# 09.net
KiCad netlist of a schematic drawn in Altium Designer
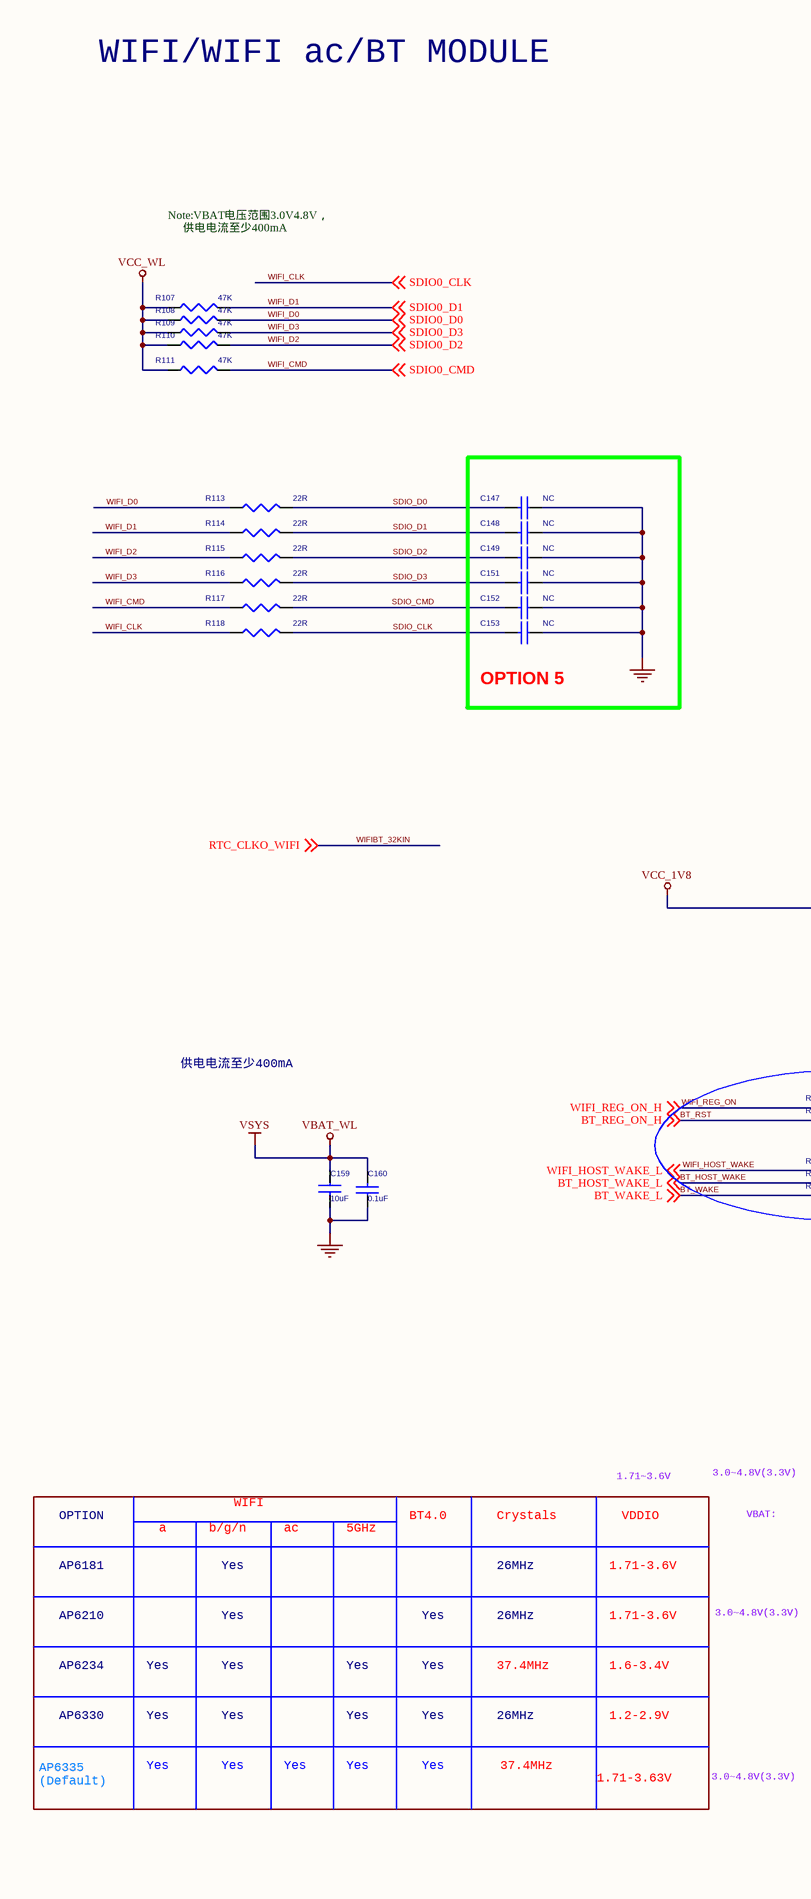
[diagram p0: 09.SchDoc, left]
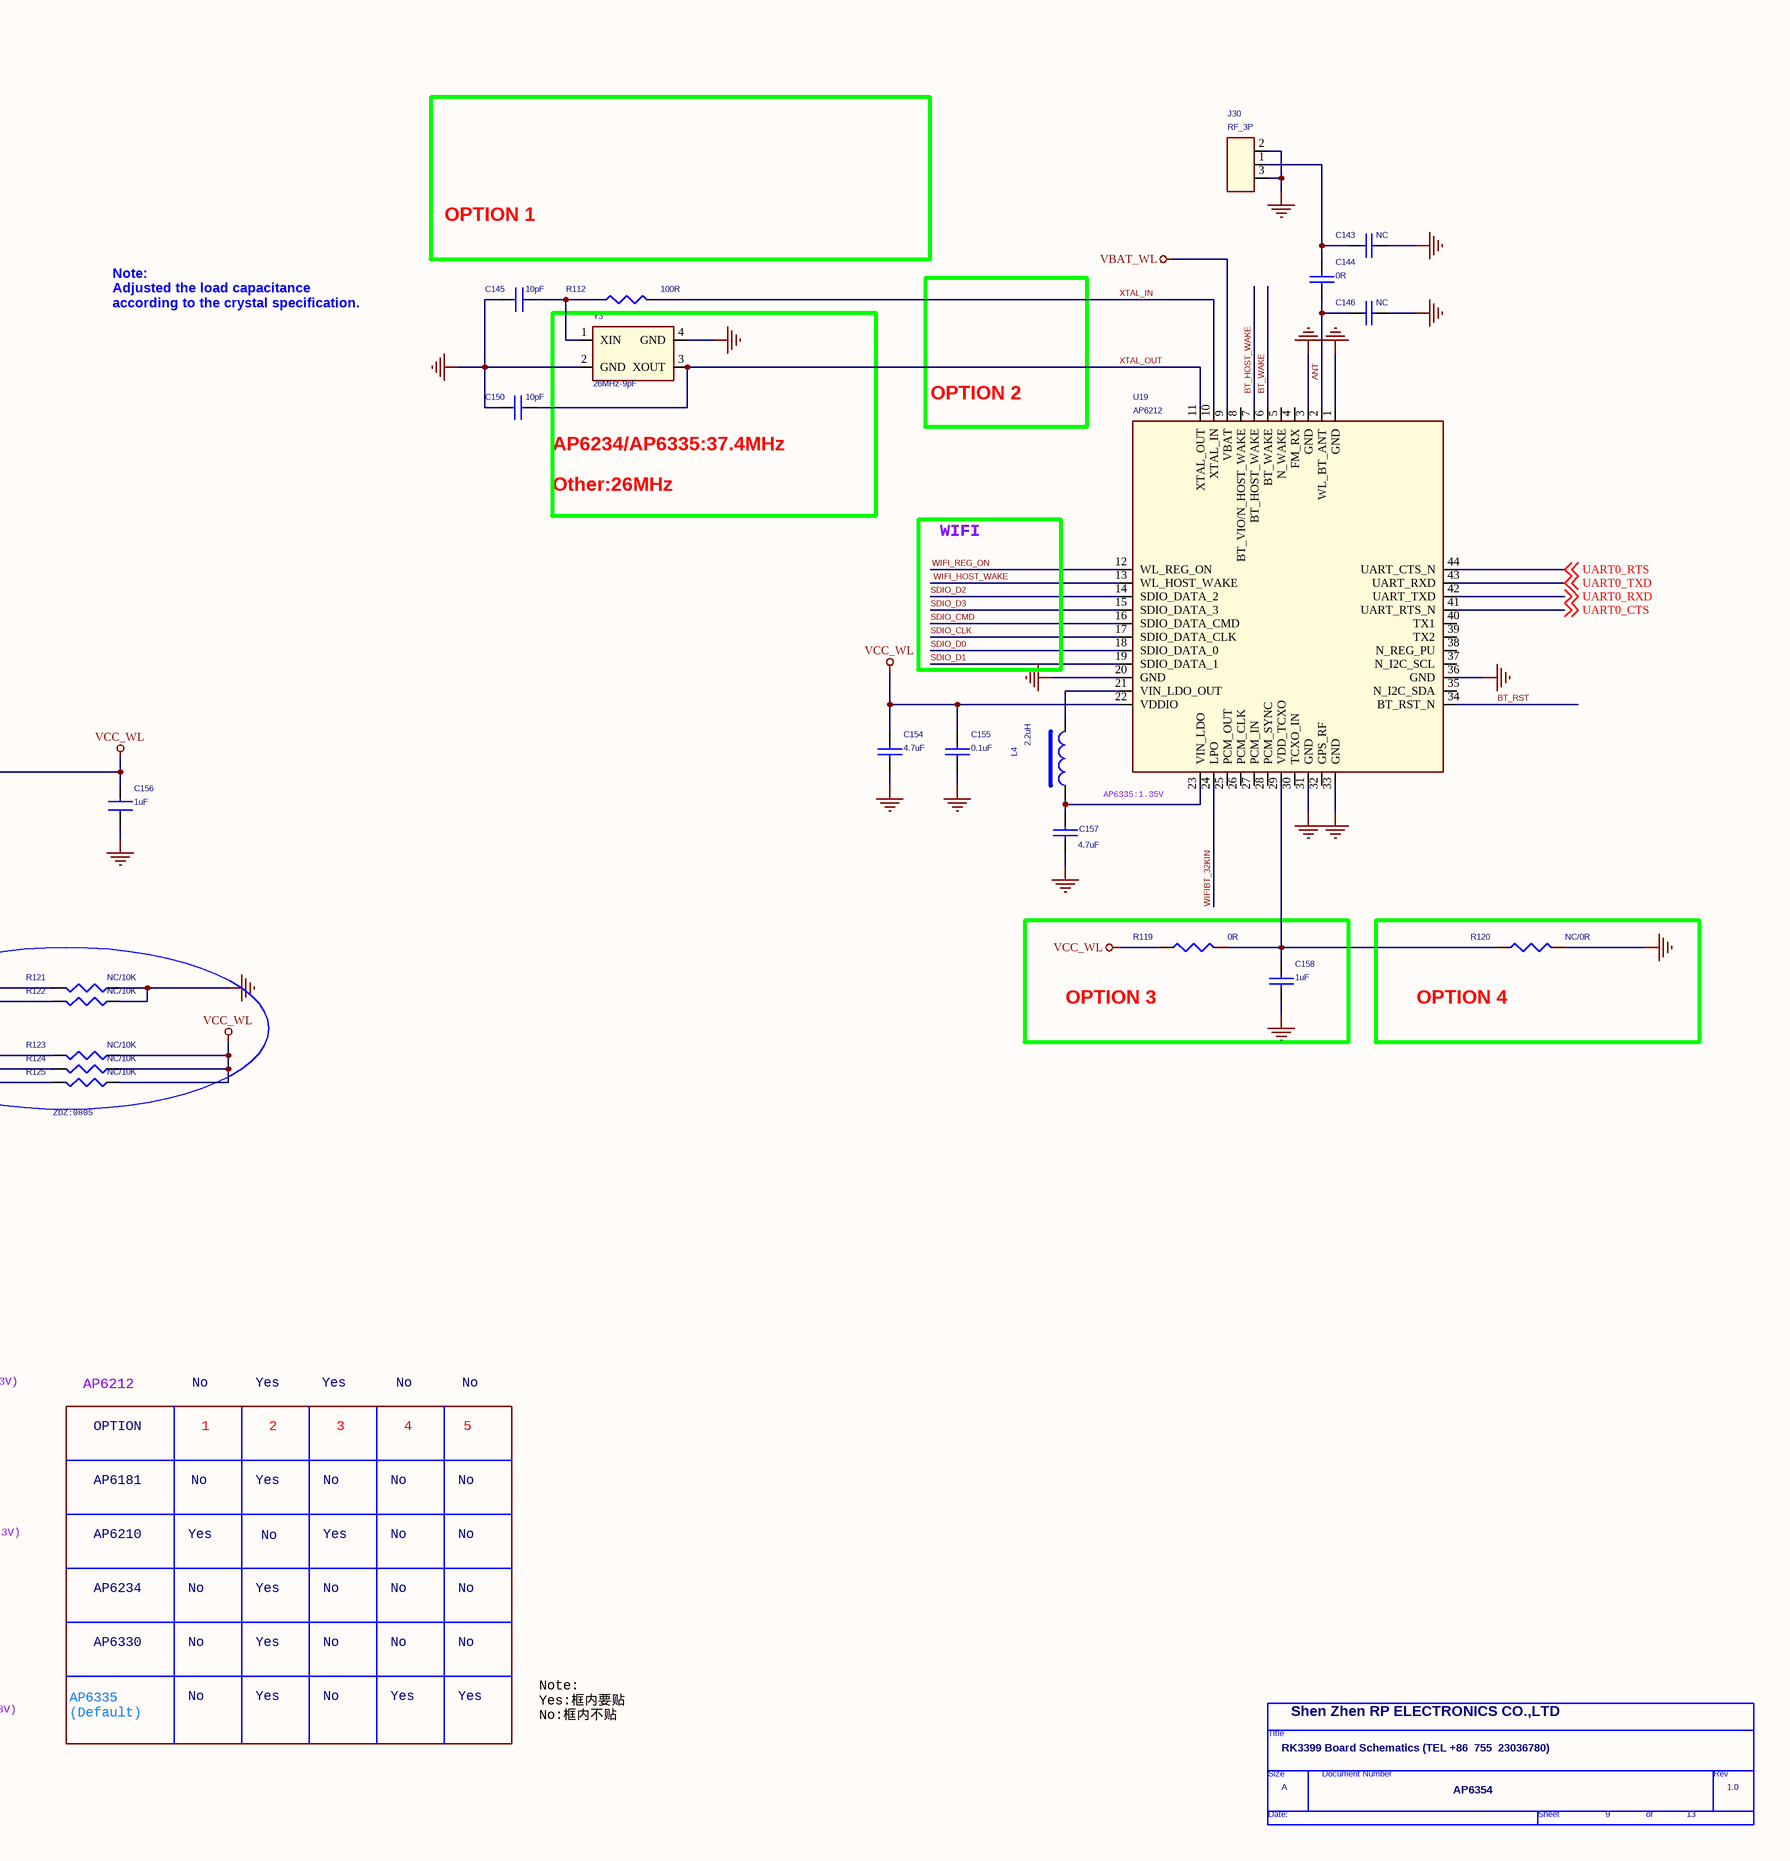
[diagram p1: 09.SchDoc, right]

(export (version "E")
  (design (tool "Eeschema 10.0.6"))
  (components
    (comp (ref "C143") (value "NC") (libsource (lib "*") (part "CAPNP_Dup1_1")))
    (comp (ref "C144") (value "0R") (libsource (lib "*") (part "CAPNP_Dup1_1")))
    (comp (ref "C145")
      (value "10pF")
      (footprint "0805C")
      (description "CAP,MLCC,8pF,+/-0.5pF,NPO,6.3V,SMD0402")
      (libsource (lib "*") (part "CAP NP"))
    )
    (comp (ref "C146") (value "NC") (libsource (lib "*") (part "CAPNP_Dup1_1")))
    (comp (ref "C147")
      (value "NC")
      (footprint "0805C")
      (description "CAP,MLCC,100nF,+/-10%,X7R,6.3V,SMD0402")
      (libsource (lib "*") (part "CAP NP"))
    )
    (comp (ref "C148")
      (value "NC")
      (footprint "0805C")
      (description "CAP,MLCC,100nF,+/-10%,X7R,6.3V,SMD0402")
      (libsource (lib "*") (part "CAP NP"))
    )
    (comp (ref "C149")
      (value "NC")
      (footprint "0805C")
      (description "CAP,MLCC,100nF,+/-10%,X7R,6.3V,SMD0402")
      (libsource (lib "*") (part "CAP NP"))
    )
    (comp (ref "C150")
      (value "10pF")
      (footprint "0805C")
      (description "CAP,MLCC,8pF,+/-0.5pF,NPO,6.3V,SMD0402")
      (libsource (lib "*") (part "CAP NP"))
    )
    (comp (ref "C151")
      (value "NC")
      (footprint "0805C")
      (description "CAP,MLCC,100nF,+/-10%,X7R,6.3V,SMD0402")
      (libsource (lib "*") (part "CAP NP"))
    )
    (comp (ref "C152")
      (value "NC")
      (footprint "0805C")
      (description "CAP,MLCC,100nF,+/-10%,X7R,6.3V,SMD0402")
      (libsource (lib "*") (part "CAP NP"))
    )
    (comp (ref "C153")
      (value "NC")
      (footprint "0805C")
      (description "CAP,MLCC,100nF,+/-10%,X7R,6.3V,SMD0402")
      (libsource (lib "*") (part "CAP NP"))
    )
    (comp (ref "C154") (value "4.7uF") (libsource (lib "*") (part "CAPNP_Dup1_1")))
    (comp (ref "C155") (value "0.1uF") (libsource (lib "*") (part "CAPNP_Dup1_1")))
    (comp (ref "C156")
      (value "1uF")
      (footprint "0805C")
      (description "CAP,MLCC,100nF,+/-10%,X7R,6.3V,SMD0402")
      (libsource (lib "*") (part "CAP NP_Dup6"))
    )
    (comp (ref "C157") (value "4.7uF") (libsource (lib "*") (part "CAPNP_Dup1_1")))
    (comp (ref "C158") (value "1uF") (libsource (lib "*") (part "CAPNP_Dup1_1")))
    (comp (ref "C159")
      (value "10uF")
      (footprint "0805C")
      (description "CAP,MLCC,4.7uF,+/-10%,X5R,6.3V,SMD0603")
      (libsource (lib "*") (part "CAP NP"))
    )
    (comp (ref "C160")
      (value "0.1uF")
      (footprint "0805C")
      (description "CAP,MLCC,100nF,+/-10%,X7R,6.3V,SMD0402")
      (libsource (lib "*") (part "CAP NP"))
    )
    (comp (ref "J30") (value "RF_3P") (libsource (lib "*") (part "CON3_1")))
    (comp (ref "L4")
      (value "2.2uH")
      (description "CoilInd,Shielded(SHLD),2.2uH@100KHz,+/-30%,1.09A,110mOhm,SMD,3.0*3.0*1.0")
      (libsource (lib "*") (part "INDUCTOR_1_Dup1"))
    )
    (comp (ref "R107")
      (value "47K")
      (footprint "0805")
      (description "ROHS CHIP RES 10K 1/16W +/-5%")
      (libsource (lib "*") (part "RESISTOR_Dup2"))
    )
    (comp (ref "R108")
      (value "47K")
      (footprint "0805")
      (description "ROHS CHIP RES 10K 1/16W +/-5%")
      (libsource (lib "*") (part "RESISTOR_Dup2"))
    )
    (comp (ref "R109")
      (value "47K")
      (footprint "0805")
      (description "ROHS CHIP RES 10K 1/16W +/-5%")
      (libsource (lib "*") (part "RESISTOR_Dup2"))
    )
    (comp (ref "R110")
      (value "47K")
      (footprint "0805")
      (description "ROHS CHIP RES 10K 1/16W +/-5%")
      (libsource (lib "*") (part "RESISTOR_Dup2"))
    )
    (comp (ref "R111")
      (value "47K")
      (footprint "0805")
      (description "ROHS CHIP RES 10K 1/16W +/-5%")
      (libsource (lib "*") (part "RESISTOR_Dup2"))
    )
    (comp (ref "R112") (value "100R") (footprint "0805") (libsource (lib "*") (part "R_0")))
    (comp (ref "R113")
      (value "22R")
      (footprint "0805")
      (description "RES,thick film,33Ohm,+/-5%,1/16W,SMD0402")
      (libsource (lib "*") (part "RESISTOR_Dup2"))
    )
    (comp (ref "R114")
      (value "22R")
      (footprint "0805")
      (description "RES,thick film,33Ohm,+/-5%,1/16W,SMD0402")
      (libsource (lib "*") (part "RESISTOR_Dup2"))
    )
    (comp (ref "R115")
      (value "22R")
      (footprint "0805")
      (description "RES,thick film,33Ohm,+/-5%,1/16W,SMD0402")
      (libsource (lib "*") (part "RESISTOR_Dup2"))
    )
    (comp (ref "R116")
      (value "22R")
      (footprint "0805")
      (description "RES,thick film,33Ohm,+/-5%,1/16W,SMD0402")
      (libsource (lib "*") (part "RESISTOR_Dup2"))
    )
    (comp (ref "R117")
      (value "22R")
      (footprint "0805")
      (description "RES,thick film,33Ohm,+/-5%,1/16W,SMD0402")
      (libsource (lib "*") (part "RESISTOR_Dup2"))
    )
    (comp (ref "R118")
      (value "22R")
      (footprint "0805")
      (description "RES,thick film,33Ohm,+/-5%,1/16W,SMD0402")
      (libsource (lib "*") (part "RESISTOR_Dup2"))
    )
    (comp (ref "R119")
      (value "0R")
      (footprint "0805")
      (description "RES,thick film,33Ohm,+/-5%,1/16W,SMD0402")
      (libsource (lib "*") (part "RESISTOR_Dup2"))
    )
    (comp (ref "R120")
      (value "NC/0R")
      (footprint "0805")
      (description "RES,thick film,33Ohm,+/-5%,1/16W,SMD0402")
      (libsource (lib "*") (part "RESISTOR_Dup2"))
    )
    (comp (ref "R121") (value "NC/10K") (footprint "0805") (libsource (lib "*") (part "RESISTOR_1")))
    (comp (ref "R122") (value "NC/10K") (footprint "0805") (libsource (lib "*") (part "RESISTOR_1")))
    (comp (ref "R123") (value "NC/10K") (footprint "0805") (libsource (lib "*") (part "RESISTOR_1")))
    (comp (ref "R124") (value "NC/10K") (footprint "0805") (libsource (lib "*") (part "RESISTOR_1")))
    (comp (ref "R125") (value "NC/10K") (footprint "0805") (libsource (lib "*") (part "RESISTOR_1")))
    (comp (ref "U19") (value "AP6212") (libsource (lib "*") (part "AP6493_1")))
    (comp (ref "Y3")
      (value "26MHz-9pF")
      (footprint "CRY-3225")
      (description "Crystal,37.400MHz,+/-20ppm,12pF,SMD3225,-10°C ~ +60   °C")
      (libsource (lib "*") (part "CRYSTAL-4_4"))
    )
  )
  (nets
    (net (code "1") (name "/ANT") (class "Default")
      (node (ref "C144") (pin "1") (pinfunction "1_1") (pintype "passive"))
      (node (ref "C146") (pin "1") (pinfunction "1_1") (pintype "passive"))
      (node (ref "U19") (pin "2") (pinfunction "WL_BT_ANT_2") (pintype "passive"))
    )
    (net (code "2") (name "/SDIO_CLK") (class "Default")
      (node (ref "C153") (pin "2") (pinfunction "2_2") (pintype "passive"))
      (node (ref "R118") (pin "2") (pinfunction "2_2") (pintype "passive"))
      (node (ref "U19") (pin "17") (pinfunction "SDIO_DATA_CLK_17") (pintype "passive"))
    )
    (net (code "3") (name "/SDIO_CMD") (class "Default")
      (node (ref "C152") (pin "2") (pinfunction "2_2") (pintype "passive"))
      (node (ref "R117") (pin "2") (pinfunction "2_2") (pintype "passive"))
      (node (ref "U19") (pin "16") (pinfunction "SDIO_DATA_CMD_16") (pintype "passive"))
    )
    (net (code "4") (name "/SDIO_D0") (class "Default")
      (node (ref "C147") (pin "2") (pinfunction "2_2") (pintype "passive"))
      (node (ref "R113") (pin "2") (pinfunction "2_2") (pintype "passive"))
      (node (ref "U19") (pin "18") (pinfunction "SDIO_DATA_0_18") (pintype "passive"))
    )
    (net (code "5") (name "/SDIO_D1") (class "Default")
      (node (ref "C148") (pin "2") (pinfunction "2_2") (pintype "passive"))
      (node (ref "R114") (pin "2") (pinfunction "2_2") (pintype "passive"))
      (node (ref "U19") (pin "19") (pinfunction "SDIO_DATA_1_19") (pintype "passive"))
    )
    (net (code "6") (name "/SDIO_D2") (class "Default")
      (node (ref "C149") (pin "2") (pinfunction "2_2") (pintype "passive"))
      (node (ref "R115") (pin "2") (pinfunction "2_2") (pintype "passive"))
      (node (ref "U19") (pin "14") (pinfunction "SDIO_DATA_2_14") (pintype "passive"))
    )
    (net (code "7") (name "/SDIO_D3") (class "Default")
      (node (ref "C151") (pin "2") (pinfunction "2_2") (pintype "passive"))
      (node (ref "R116") (pin "2") (pinfunction "2_2") (pintype "passive"))
      (node (ref "U19") (pin "15") (pinfunction "SDIO_DATA_3_15") (pintype "passive"))
    )
    (net (code "8") (name "/XTAL_IN") (class "Default")
      (node (ref "R112") (pin "2") (pinfunction "2_2") (pintype "passive"))
      (node (ref "U19") (pin "10") (pinfunction "XTAL_IN_10") (pintype "passive"))
    )
    (net (code "9") (name "/XTAL_OUT") (class "Default")
      (node (ref "C150") (pin "2") (pinfunction "2_2") (pintype "passive"))
      (node (ref "U19") (pin "11") (pinfunction "XTAL_OUT_11") (pintype "passive"))
      (node (ref "Y3") (pin "3") (pinfunction "XOUT_3") (pintype "passive"))
    )
    (net (code "10") (name "BT_HOST_WAKE_L") (class "Default")
      (node (ref "R124") (pin "2") (pinfunction "2_2") (pintype "passive"))
      (node (ref "U19") (pin "7") (pinfunction "BT_HOST_WAKE_7") (pintype "passive"))
    )
    (net (code "11") (name "BT_REG_ON_H") (class "Default")
      (node (ref "R122") (pin "2") (pinfunction "2_2") (pintype "passive"))
      (node (ref "U19") (pin "34") (pinfunction "BT_RST_N_34") (pintype "passive"))
    )
    (net (code "12") (name "BT_WAKE_L") (class "Default")
      (node (ref "R125") (pin "2") (pinfunction "2_2") (pintype "passive"))
      (node (ref "U19") (pin "6") (pinfunction "BT_WAKE_6") (pintype "passive"))
    )
    (net (code "13") (name "GND") (class "Default")
      (node (ref "C143") (pin "2") (pinfunction "2_2") (pintype "passive"))
      (node (ref "C145") (pin "2") (pinfunction "2_2") (pintype "passive"))
      (node (ref "C146") (pin "2") (pinfunction "2_2") (pintype "passive"))
      (node (ref "C147") (pin "1") (pinfunction "1_1") (pintype "passive"))
      (node (ref "C148") (pin "1") (pinfunction "1_1") (pintype "passive"))
      (node (ref "C149") (pin "1") (pinfunction "1_1") (pintype "passive"))
      (node (ref "C150") (pin "1") (pinfunction "1_1") (pintype "passive"))
      (node (ref "C151") (pin "1") (pinfunction "1_1") (pintype "passive"))
      (node (ref "C152") (pin "1") (pinfunction "1_1") (pintype "passive"))
      (node (ref "C153") (pin "1") (pinfunction "1_1") (pintype "passive"))
      (node (ref "C154") (pin "1") (pinfunction "1_1") (pintype "passive"))
      (node (ref "C155") (pin "1") (pinfunction "1_1") (pintype "passive"))
      (node (ref "C156") (pin "2") (pinfunction "2_2") (pintype "passive"))
      (node (ref "C157") (pin "1") (pinfunction "1_1") (pintype "passive"))
      (node (ref "C158") (pin "1") (pinfunction "1_1") (pintype "passive"))
      (node (ref "C159") (pin "2") (pinfunction "2_2") (pintype "passive"))
      (node (ref "C160") (pin "1") (pinfunction "1_1") (pintype "passive"))
      (node (ref "J30") (pin "2") (pinfunction "2_2") (pintype "passive"))
      (node (ref "J30") (pin "3") (pinfunction "3_3") (pintype "passive"))
      (node (ref "R120") (pin "1") (pinfunction "1_1") (pintype "passive"))
      (node (ref "R121") (pin "1") (pinfunction "1_1") (pintype "passive"))
      (node (ref "R122") (pin "1") (pinfunction "1_1") (pintype "passive"))
      (node (ref "U19") (pin "1") (pinfunction "GND_1") (pintype "power_in"))
      (node (ref "U19") (pin "20") (pinfunction "GND_20") (pintype "power_in"))
      (node (ref "U19") (pin "3") (pinfunction "GND_3") (pintype "power_in"))
      (node (ref "U19") (pin "31") (pinfunction "GND_31") (pintype "power_in"))
      (node (ref "U19") (pin "33") (pinfunction "GND_33") (pintype "power_in"))
      (node (ref "U19") (pin "36") (pinfunction "GND_36") (pintype "power_in"))
      (node (ref "Y3") (pin "2") (pinfunction "GND_2") (pintype "power_in"))
      (node (ref "Y3") (pin "4") (pinfunction "GND_4") (pintype "power_in"))
    )
    (net (code "14") (name "Net-(C143-Pad1)") (class "Default")
      (node (ref "C143") (pin "1") (pinfunction "1_1") (pintype "passive"))
      (node (ref "C144") (pin "2") (pinfunction "2_2") (pintype "passive"))
      (node (ref "J30") (pin "1") (pinfunction "1_1") (pintype "passive"))
    )
    (net (code "15") (name "Net-(U19-VDD_TCXO)") (class "Default")
      (node (ref "C158") (pin "2") (pinfunction "2_2") (pintype "passive"))
      (node (ref "R119") (pin "1") (pinfunction "1_1") (pintype "passive"))
      (node (ref "R120") (pin "2") (pinfunction "2_2") (pintype "passive"))
      (node (ref "U19") (pin "29") (pinfunction "VDD_TCXO_29") (pintype "passive"))
    )
    (net (code "16") (name "Net-(U19-VIN_LDO)") (class "Default")
      (node (ref "C157") (pin "2") (pinfunction "2_2") (pintype "passive"))
      (node (ref "L4") (pin "1") (pinfunction "1_1") (pintype "passive"))
      (node (ref "U19") (pin "23") (pinfunction "VIN_LDO_23") (pintype "passive"))
    )
    (net (code "17") (name "Net-(U19-VIN_LDO_OUT)") (class "Default")
      (node (ref "L4") (pin "2") (pinfunction "2_2") (pintype "passive"))
      (node (ref "U19") (pin "21") (pinfunction "VIN_LDO_OUT_21") (pintype "passive"))
    )
    (net (code "18") (name "Net-(Y3-XIN)") (class "Default")
      (node (ref "C145") (pin "1") (pinfunction "1_1") (pintype "passive"))
      (node (ref "R112") (pin "1") (pinfunction "1_1") (pintype "passive"))
      (node (ref "Y3") (pin "1") (pinfunction "XIN_1") (pintype "passive"))
    )
    (net (code "19") (name "RTC_CLKO_WIFI") (class "Default")
      (node (ref "U19") (pin "24") (pinfunction "LPO_24") (pintype "passive"))
    )
    (net (code "20") (name "SDIO0_CLK") (class "Default")
      (node (ref "R118") (pin "1") (pinfunction "1_1") (pintype "passive"))
    )
    (net (code "21") (name "SDIO0_CMD") (class "Default")
      (node (ref "R111") (pin "2") (pinfunction "2_2") (pintype "passive"))
      (node (ref "R117") (pin "1") (pinfunction "1_1") (pintype "passive"))
    )
    (net (code "22") (name "SDIO0_D0") (class "Default")
      (node (ref "R108") (pin "2") (pinfunction "2_2") (pintype "passive"))
      (node (ref "R113") (pin "1") (pinfunction "1_1") (pintype "passive"))
    )
    (net (code "23") (name "SDIO0_D1") (class "Default")
      (node (ref "R107") (pin "2") (pinfunction "2_2") (pintype "passive"))
      (node (ref "R114") (pin "1") (pinfunction "1_1") (pintype "passive"))
    )
    (net (code "24") (name "SDIO0_D2") (class "Default")
      (node (ref "R110") (pin "2") (pinfunction "2_2") (pintype "passive"))
      (node (ref "R115") (pin "1") (pinfunction "1_1") (pintype "passive"))
    )
    (net (code "25") (name "SDIO0_D3") (class "Default")
      (node (ref "R109") (pin "2") (pinfunction "2_2") (pintype "passive"))
      (node (ref "R116") (pin "1") (pinfunction "1_1") (pintype "passive"))
    )
    (net (code "26") (name "UART0_CTS") (class "Default")
      (node (ref "U19") (pin "41") (pinfunction "UART_RTS_N_41") (pintype "passive"))
    )
    (net (code "27") (name "UART0_RTS") (class "Default")
      (node (ref "U19") (pin "44") (pinfunction "UART_CTS_N_44") (pintype "passive"))
    )
    (net (code "28") (name "UART0_RXD") (class "Default")
      (node (ref "U19") (pin "42") (pinfunction "UART_TXD_42") (pintype "passive"))
    )
    (net (code "29") (name "UART0_TXD") (class "Default")
      (node (ref "U19") (pin "43") (pinfunction "UART_RXD_43") (pintype "passive"))
    )
    (net (code "30") (name "VBAT_WL") (class "Default")
      (node (ref "C159") (pin "1") (pinfunction "1_1") (pintype "passive"))
      (node (ref "C160") (pin "2") (pinfunction "2_2") (pintype "passive"))
      (node (ref "U19") (pin "9") (pinfunction "VBAT_9") (pintype "passive"))
    )
    (net (code "31") (name "VCC_1V8") (class "Default")
      (node (ref "C154") (pin "2") (pinfunction "2_2") (pintype "passive"))
      (node (ref "C155") (pin "2") (pinfunction "2_2") (pintype "passive"))
      (node (ref "C156") (pin "1") (pinfunction "1_1") (pintype "passive"))
      (node (ref "R107") (pin "1") (pinfunction "1_1") (pintype "passive"))
      (node (ref "R108") (pin "1") (pinfunction "1_1") (pintype "passive"))
      (node (ref "R109") (pin "1") (pinfunction "1_1") (pintype "passive"))
      (node (ref "R110") (pin "1") (pinfunction "1_1") (pintype "passive"))
      (node (ref "R111") (pin "1") (pinfunction "1_1") (pintype "passive"))
      (node (ref "R119") (pin "2") (pinfunction "2_2") (pintype "passive"))
      (node (ref "R123") (pin "1") (pinfunction "1_1") (pintype "passive"))
      (node (ref "R124") (pin "1") (pinfunction "1_1") (pintype "passive"))
      (node (ref "R125") (pin "1") (pinfunction "1_1") (pintype "passive"))
      (node (ref "U19") (pin "22") (pinfunction "VDDIO_22") (pintype "passive"))
    )
    (net (code "32") (name "WIFI_HOST_WAKE_L") (class "Default")
      (node (ref "R123") (pin "2") (pinfunction "2_2") (pintype "passive"))
      (node (ref "U19") (pin "13") (pinfunction "WL_HOST_WAKE_13") (pintype "passive"))
    )
    (net (code "33") (name "WIFI_REG_ON_H") (class "Default")
      (node (ref "R121") (pin "2") (pinfunction "2_2") (pintype "passive"))
      (node (ref "U19") (pin "12") (pinfunction "WL_REG_ON_12") (pintype "passive"))
    )
    (net (code "34") (name "unconnected-(U19-BT_VIO{slash}N_HOST_WAKE-Pad8)") (class "Default")
      (node (ref "U19") (pin "8") (pinfunction "BT_VIO/N_HOST_WAKE_8") (pintype "passive"))
    )
    (net (code "35") (name "unconnected-(U19-FM_RX-Pad4)") (class "Default")
      (node (ref "U19") (pin "4") (pinfunction "FM_RX_4") (pintype "passive"))
    )
    (net (code "36") (name "unconnected-(U19-GPS_RF-Pad32)") (class "Default")
      (node (ref "U19") (pin "32") (pinfunction "GPS_RF_32") (pintype "passive"))
    )
    (net (code "37") (name "unconnected-(U19-N_I2C_SCL-Pad37)") (class "Default")
      (node (ref "U19") (pin "37") (pinfunction "N_I2C_SCL_37") (pintype "passive"))
    )
    (net (code "38") (name "unconnected-(U19-N_I2C_SDA-Pad35)") (class "Default")
      (node (ref "U19") (pin "35") (pinfunction "N_I2C_SDA_35") (pintype "passive"))
    )
    (net (code "39") (name "unconnected-(U19-N_REG_PU-Pad38)") (class "Default")
      (node (ref "U19") (pin "38") (pinfunction "N_REG_PU_38") (pintype "passive"))
    )
    (net (code "40") (name "unconnected-(U19-N_WAKE-Pad5)") (class "Default")
      (node (ref "U19") (pin "5") (pinfunction "N_WAKE_5") (pintype "passive"))
    )
    (net (code "41") (name "unconnected-(U19-PCM_CLK-Pad26)") (class "Default")
      (node (ref "U19") (pin "26") (pinfunction "PCM_CLK_26") (pintype "passive"))
    )
    (net (code "42") (name "unconnected-(U19-PCM_IN-Pad27)") (class "Default")
      (node (ref "U19") (pin "27") (pinfunction "PCM_IN_27") (pintype "passive"))
    )
    (net (code "43") (name "unconnected-(U19-PCM_OUT-Pad25)") (class "Default")
      (node (ref "U19") (pin "25") (pinfunction "PCM_OUT_25") (pintype "passive"))
    )
    (net (code "44") (name "unconnected-(U19-PCM_SYNC-Pad28)") (class "Default")
      (node (ref "U19") (pin "28") (pinfunction "PCM_SYNC_28") (pintype "passive"))
    )
    (net (code "45") (name "unconnected-(U19-TCXO_IN-Pad30)") (class "Default")
      (node (ref "U19") (pin "30") (pinfunction "TCXO_IN_30") (pintype "passive"))
    )
    (net (code "46") (name "unconnected-(U19-TX1-Pad40)") (class "Default")
      (node (ref "U19") (pin "40") (pinfunction "TX1_40") (pintype "passive"))
    )
    (net (code "47") (name "unconnected-(U19-TX2-Pad39)") (class "Default")
      (node (ref "U19") (pin "39") (pinfunction "TX2_39") (pintype "passive"))
    )
  )
)
